# RC_prueba.net
KiCad netlist of a schematic drawn in EAGLE
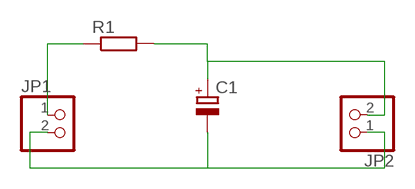
[diagram p0: schematic, sheet 1]

(export (version "E")
  (design (tool "Eeschema 10.0.6"))
  (components
    (comp (ref "C1")
      (value "CPOL-EUA/3216-18R")
      (footprint "eagle-import:A_3216-18R")
      (libsource (lib "eagle-import") (part "CPOL-EUA/3216-18R"))
    )
    (comp (ref "JP1")
      (value "PINHD-1X2")
      (footprint "eagle-import:1X02")
      (libsource (lib "eagle-import") (part "PINHD-1X2"))
    )
    (comp (ref "JP2")
      (value "PINHD-1X2")
      (footprint "eagle-import:1X02")
      (libsource (lib "eagle-import") (part "PINHD-1X2"))
    )
    (comp (ref "R1")
      (value "R-EU_MELF0204W")
      (footprint "eagle-import:MINI_MELF-0204W")
      (libsource (lib "eagle-import") (part "R-EU_MELF0204W"))
    )
  )
  (nets
    (net (code "1") (name "Net-(C1-Pad+)") (class "Default")
      (node (ref "C1") (pin "+") (pinfunction "+_+") (pintype "passive"))
      (node (ref "JP2") (pin "2") (pinfunction "2_2") (pintype "passive"))
      (node (ref "R1") (pin "2") (pinfunction "2_2") (pintype "passive"))
    )
    (net (code "2") (name "Net-(C1-Pad-)") (class "Default")
      (node (ref "C1") (pin "-") (pinfunction "-_-") (pintype "passive"))
      (node (ref "JP1") (pin "2") (pinfunction "2_2") (pintype "passive"))
      (node (ref "JP2") (pin "1") (pinfunction "1_1") (pintype "passive"))
    )
    (net (code "3") (name "Net-(JP1-Pad1)") (class "Default")
      (node (ref "JP1") (pin "1") (pinfunction "1_1") (pintype "passive"))
      (node (ref "R1") (pin "1") (pinfunction "1_1") (pintype "passive"))
    )
  )
)
